# RELAY.net
KiCad netlist of a schematic drawn in Altium Designer
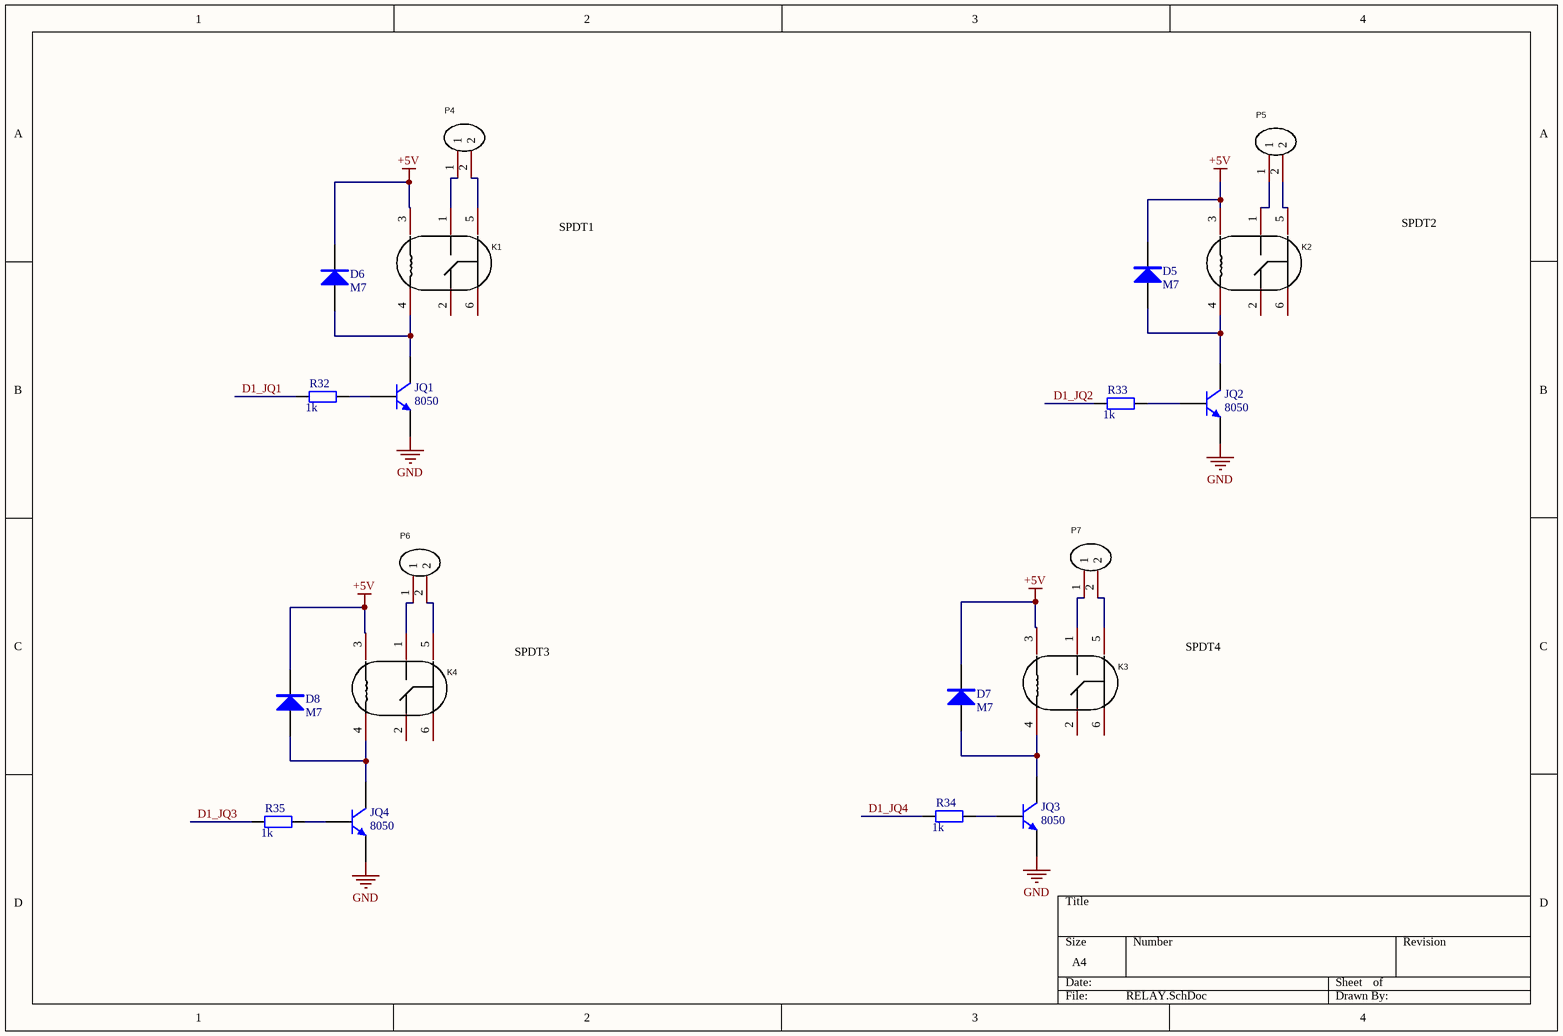
[diagram p0: RELAY.SchDoc]

(export (version "E")
  (design (tool "Eeschema 10.0.6"))
  (components
    (comp (ref "D5")
      (value "M7")
      (footprint "DO-214AC")
      (description "二极管")
      (libsource (lib "常用器件") (part "DIODE"))
    )
    (comp (ref "D6")
      (value "M7")
      (footprint "DO-214AC")
      (description "二极管")
      (libsource (lib "常用器件") (part "DIODE"))
    )
    (comp (ref "D7")
      (value "M7")
      (footprint "DO-214AC")
      (description "二极管")
      (libsource (lib "常用器件") (part "DIODE"))
    )
    (comp (ref "D8")
      (value "M7")
      (footprint "DO-214AC")
      (description "二极管")
      (libsource (lib "常用器件") (part "DIODE"))
    )
    (comp (ref "JQ1") (value "8050") (footprint "SOT-23-3_(三极管)") (libsource (lib "泰开常用器件(3)") (part "NPN")))
    (comp (ref "JQ2") (value "8050") (footprint "SOT-23-3_(三极管)") (libsource (lib "泰开常用器件(3)") (part "NPN")))
    (comp (ref "JQ3") (value "8050") (footprint "SOT-23-3_(三极管)") (libsource (lib "泰开常用器件(3)") (part "NPN")))
    (comp (ref "JQ4") (value "8050") (footprint "SOT-23-3_(三极管)") (libsource (lib "泰开常用器件(3)") (part "NPN")))
    (comp (ref "K1")
      (value "HK4100F-DC5V-SHG")
      (footprint "HK4100F")
      (fields (field (name "MANUFACTURER") "汇科"))
      (libsource (lib "继电器") (part "HK4100F-DC5V-SHG"))
    )
    (comp (ref "K2")
      (value "HK4100F-DC5V-SHG")
      (footprint "HK4100F")
      (fields (field (name "MANUFACTURER") "汇科"))
      (libsource (lib "继电器") (part "HK4100F-DC5V-SHG"))
    )
    (comp (ref "K3")
      (value "HK4100F-DC5V-SHG")
      (footprint "HK4100F")
      (fields (field (name "MANUFACTURER") "汇科"))
      (libsource (lib "继电器") (part "HK4100F-DC5V-SHG"))
    )
    (comp (ref "K4")
      (value "HK4100F-DC5V-SHG")
      (footprint "HK4100F")
      (fields (field (name "MANUFACTURER") "汇科"))
      (libsource (lib "继电器") (part "HK4100F-DC5V-SHG"))
    )
    (comp (ref "P4")
      (value "WJ500V-5.08-2P")
      (footprint "KF128-2P DG128")
      (fields (field (name "MANUFACTURER") "KANGNEX(康奈克斯电气)"))
      (libsource (lib "泰开常用器件") (part "WJ500V-5.08-2P"))
    )
    (comp (ref "P5")
      (value "WJ500V-5.08-2P")
      (footprint "KF128-2P DG128")
      (fields (field (name "MANUFACTURER") "KANGNEX(康奈克斯电气)"))
      (libsource (lib "泰开常用器件") (part "WJ500V-5.08-2P"))
    )
    (comp (ref "P6")
      (value "WJ500V-5.08-2P")
      (footprint "KF128-2P DG128")
      (fields (field (name "MANUFACTURER") "KANGNEX(康奈克斯电气)"))
      (libsource (lib "泰开常用器件") (part "WJ500V-5.08-2P"))
    )
    (comp (ref "P7")
      (value "WJ500V-5.08-2P")
      (footprint "KF128-2P DG128")
      (fields (field (name "MANUFACTURER") "KANGNEX(康奈克斯电气)"))
      (libsource (lib "泰开常用器件") (part "WJ500V-5.08-2P"))
    )
    (comp (ref "R32")
      (value "1k")
      (footprint "R-0805")
      (description "电阻")
      (fields (field (name "PUBLISHER") "Altium Limited"))
      (libsource (lib "泰开常用器件") (part "RES"))
    )
    (comp (ref "R33")
      (value "1k")
      (footprint "R-0805")
      (description "电阻")
      (fields (field (name "PUBLISHER") "Altium Limited"))
      (libsource (lib "泰开常用器件") (part "RES"))
    )
    (comp (ref "R34")
      (value "1k")
      (footprint "R-0805")
      (description "电阻")
      (fields (field (name "PUBLISHER") "Altium Limited"))
      (libsource (lib "泰开常用器件") (part "RES"))
    )
    (comp (ref "R35")
      (value "1k")
      (footprint "R-0805")
      (description "电阻")
      (fields (field (name "PUBLISHER") "Altium Limited"))
      (libsource (lib "泰开常用器件") (part "RES"))
    )
  )
  (nets
    (net (code "1") (name "+5V") (class "Default")
      (node (ref "D5") (pin "2") (pinfunction "K_2") (pintype "passive"))
      (node (ref "D6") (pin "2") (pinfunction "K_2") (pintype "passive"))
      (node (ref "D7") (pin "2") (pinfunction "K_2") (pintype "passive"))
      (node (ref "D8") (pin "2") (pinfunction "K_2") (pintype "passive"))
      (node (ref "K1") (pin "3") (pinfunction "3_3") (pintype "passive"))
      (node (ref "K2") (pin "3") (pinfunction "3_3") (pintype "passive"))
      (node (ref "K3") (pin "3") (pinfunction "3_3") (pintype "passive"))
      (node (ref "K4") (pin "3") (pinfunction "3_3") (pintype "passive"))
    )
    (net (code "2") (name "/D1_JQ1") (class "Default")
      (node (ref "R32") (pin "2") (pinfunction "2_2") (pintype "passive"))
    )
    (net (code "3") (name "/D1_JQ2") (class "Default")
      (node (ref "R33") (pin "2") (pinfunction "2_2") (pintype "passive"))
    )
    (net (code "4") (name "/D1_JQ3") (class "Default")
      (node (ref "R35") (pin "2") (pinfunction "2_2") (pintype "passive"))
    )
    (net (code "5") (name "/D1_JQ4") (class "Default")
      (node (ref "R34") (pin "2") (pinfunction "2_2") (pintype "passive"))
    )
    (net (code "6") (name "GND") (class "Default")
      (node (ref "JQ1") (pin "2") (pinfunction "E_2") (pintype "passive"))
      (node (ref "JQ2") (pin "2") (pinfunction "E_2") (pintype "passive"))
      (node (ref "JQ3") (pin "2") (pinfunction "E_2") (pintype "passive"))
      (node (ref "JQ4") (pin "2") (pinfunction "E_2") (pintype "passive"))
    )
    (net (code "7") (name "Net-(D5-A)") (class "Default")
      (node (ref "D5") (pin "1") (pinfunction "A_1") (pintype "passive"))
      (node (ref "JQ2") (pin "3") (pinfunction "C_3") (pintype "passive"))
      (node (ref "K2") (pin "4") (pinfunction "4_4") (pintype "passive"))
    )
    (net (code "8") (name "Net-(D6-A)") (class "Default")
      (node (ref "D6") (pin "1") (pinfunction "A_1") (pintype "passive"))
      (node (ref "JQ1") (pin "3") (pinfunction "C_3") (pintype "passive"))
      (node (ref "K1") (pin "4") (pinfunction "4_4") (pintype "passive"))
    )
    (net (code "9") (name "Net-(D7-A)") (class "Default")
      (node (ref "D7") (pin "1") (pinfunction "A_1") (pintype "passive"))
      (node (ref "JQ3") (pin "3") (pinfunction "C_3") (pintype "passive"))
      (node (ref "K3") (pin "4") (pinfunction "4_4") (pintype "passive"))
    )
    (net (code "10") (name "Net-(D8-A)") (class "Default")
      (node (ref "D8") (pin "1") (pinfunction "A_1") (pintype "passive"))
      (node (ref "JQ4") (pin "3") (pinfunction "C_3") (pintype "passive"))
      (node (ref "K4") (pin "4") (pinfunction "4_4") (pintype "passive"))
    )
    (net (code "11") (name "Net-(JQ1-B)") (class "Default")
      (node (ref "JQ1") (pin "1") (pinfunction "B_1") (pintype "passive"))
      (node (ref "R32") (pin "1") (pinfunction "1_1") (pintype "passive"))
    )
    (net (code "12") (name "Net-(JQ2-B)") (class "Default")
      (node (ref "JQ2") (pin "1") (pinfunction "B_1") (pintype "passive"))
      (node (ref "R33") (pin "1") (pinfunction "1_1") (pintype "passive"))
    )
    (net (code "13") (name "Net-(JQ3-B)") (class "Default")
      (node (ref "JQ3") (pin "1") (pinfunction "B_1") (pintype "passive"))
      (node (ref "R34") (pin "1") (pinfunction "1_1") (pintype "passive"))
    )
    (net (code "14") (name "Net-(JQ4-B)") (class "Default")
      (node (ref "JQ4") (pin "1") (pinfunction "B_1") (pintype "passive"))
      (node (ref "R35") (pin "1") (pinfunction "1_1") (pintype "passive"))
    )
    (net (code "15") (name "Net-(K1-Pad1)") (class "Default")
      (node (ref "K1") (pin "1") (pinfunction "1_1") (pintype "passive"))
      (node (ref "P4") (pin "1") (pinfunction "1_1") (pintype "passive"))
    )
    (net (code "16") (name "Net-(K1-Pad5)") (class "Default")
      (node (ref "K1") (pin "5") (pinfunction "5_5") (pintype "passive"))
      (node (ref "P4") (pin "2") (pinfunction "2_2") (pintype "passive"))
    )
    (net (code "17") (name "Net-(K2-Pad1)") (class "Default")
      (node (ref "K2") (pin "1") (pinfunction "1_1") (pintype "passive"))
      (node (ref "P5") (pin "1") (pinfunction "1_1") (pintype "passive"))
    )
    (net (code "18") (name "Net-(K2-Pad5)") (class "Default")
      (node (ref "K2") (pin "5") (pinfunction "5_5") (pintype "passive"))
      (node (ref "P5") (pin "2") (pinfunction "2_2") (pintype "passive"))
    )
    (net (code "19") (name "Net-(K3-Pad1)") (class "Default")
      (node (ref "K3") (pin "1") (pinfunction "1_1") (pintype "passive"))
      (node (ref "P7") (pin "1") (pinfunction "1_1") (pintype "passive"))
    )
    (net (code "20") (name "Net-(K3-Pad5)") (class "Default")
      (node (ref "K3") (pin "5") (pinfunction "5_5") (pintype "passive"))
      (node (ref "P7") (pin "2") (pinfunction "2_2") (pintype "passive"))
    )
    (net (code "21") (name "Net-(K4-Pad1)") (class "Default")
      (node (ref "K4") (pin "1") (pinfunction "1_1") (pintype "passive"))
      (node (ref "P6") (pin "1") (pinfunction "1_1") (pintype "passive"))
    )
    (net (code "22") (name "Net-(K4-Pad5)") (class "Default")
      (node (ref "K4") (pin "5") (pinfunction "5_5") (pintype "passive"))
      (node (ref "P6") (pin "2") (pinfunction "2_2") (pintype "passive"))
    )
    (net (code "23") (name "unconnected-(K1-Pad2)") (class "Default")
      (node (ref "K1") (pin "2") (pinfunction "2_2") (pintype "passive"))
    )
    (net (code "24") (name "unconnected-(K1-Pad6)") (class "Default")
      (node (ref "K1") (pin "6") (pinfunction "6_6") (pintype "passive"))
    )
    (net (code "25") (name "unconnected-(K2-Pad2)") (class "Default")
      (node (ref "K2") (pin "2") (pinfunction "2_2") (pintype "passive"))
    )
    (net (code "26") (name "unconnected-(K2-Pad6)") (class "Default")
      (node (ref "K2") (pin "6") (pinfunction "6_6") (pintype "passive"))
    )
    (net (code "27") (name "unconnected-(K3-Pad2)") (class "Default")
      (node (ref "K3") (pin "2") (pinfunction "2_2") (pintype "passive"))
    )
    (net (code "28") (name "unconnected-(K3-Pad6)") (class "Default")
      (node (ref "K3") (pin "6") (pinfunction "6_6") (pintype "passive"))
    )
    (net (code "29") (name "unconnected-(K4-Pad2)") (class "Default")
      (node (ref "K4") (pin "2") (pinfunction "2_2") (pintype "passive"))
    )
    (net (code "30") (name "unconnected-(K4-Pad6)") (class "Default")
      (node (ref "K4") (pin "6") (pinfunction "6_6") (pintype "passive"))
    )
  )
)
